# cree_lamp.net
KiCad netlist of a schematic drawn in Altium Designer
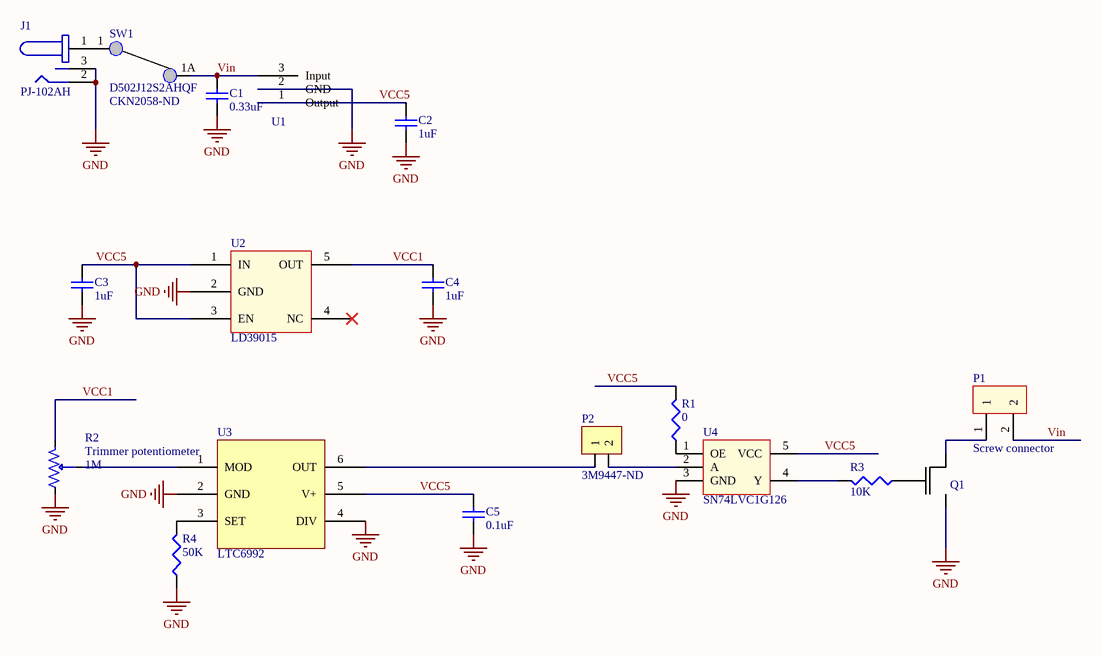
[diagram p0: cree_lamp.SchDoc]

(export (version "E")
  (design (tool "Eeschema 10.0.6"))
  (components
    (comp (ref "C1")
      (value "0.33uF")
      (footprint "1608[0603]")
      (description "Capacitor (Semiconductor SIM Model)")
      (fields (field (name "Comment") "Cap Semi") (field (name "PUBLISHER") "Altium Limited"))
      (libsource (lib "Miscellaneous Devices") (part "Cap Semi"))
    )
    (comp (ref "C2")
      (value "1uF")
      (footprint "1608[0603]")
      (description "Capacitor (Semiconductor SIM Model)")
      (fields (field (name "Comment") "Cap Semi") (field (name "PUBLISHER") "Altium Limited"))
      (libsource (lib "Miscellaneous Devices") (part "Cap Semi"))
    )
    (comp (ref "C3")
      (value "1uF")
      (footprint "1608[0603]")
      (description "Capacitor (Semiconductor SIM Model)")
      (fields (field (name "Comment") "Cap Semi") (field (name "PUBLISHER") "Altium Limited"))
      (libsource (lib "Miscellaneous Devices") (part "Cap Semi"))
    )
    (comp (ref "C4")
      (value "1uF")
      (footprint "1608[0603]")
      (description "Capacitor (Semiconductor SIM Model)")
      (fields (field (name "Comment") "Cap Semi") (field (name "PUBLISHER") "Altium Limited"))
      (libsource (lib "Miscellaneous Devices") (part "Cap Semi"))
    )
    (comp (ref "C5")
      (value "0.1uF")
      (footprint "1608[0603]")
      (description "Capacitor (Semiconductor SIM Model)")
      (fields (field (name "Comment") "Cap Semi") (field (name "PUBLISHER") "Altium Limited"))
      (libsource (lib "Miscellaneous Devices") (part "Cap Semi"))
    )
    (comp (ref "J1")
      (value "PJ-102AH")
      (footprint "PJ-102AH")
      (description "CONN PWR JACK 2.1X5.5MM HIGH CUR")
      (libsource (lib "vlc_ctrl") (part "PJ-102AH"))
    )
    (comp (ref "P1")
      (value "Screw connector")
      (footprint "MPT_2position")
      (description "Screw connector 2 positions")
      (libsource (lib "vlc_ctrl") (part "MPT_2POS"))
    )
    (comp (ref "P2")
      (value "1 x 2 header")
      (footprint "1x2 header")
      (description "100 mils standard header")
      (fields (field (name "SUPPLIER PART NUMBER 1") "3M9447-ND"))
      (libsource (lib "vlc_ctrl") (part "1 x 2 header"))
    )
    (comp (ref "Q1")
      (value "Si2312CDS")
      (footprint "SOT95P250-3N")
      (description "N-Channel 20 V (D-S) MOSFET")
      (libsource (lib "vlc_ctrl") (part "Si2312CDS"))
    )
    (comp (ref "R1")
      (value "0")
      (footprint "J1-0603")
      (description "Resistor")
      (fields (field (name "Comment") "Res3") (field (name "PUBLISHER") "Altium Limited"))
      (libsource (lib "Miscellaneous Devices") (part "Res3"))
    )
    (comp (ref "R2")
      (value "Trimmer potentiometer")
      (footprint "3386P")
      (fields (field (name "ALTIUM_VALUE") "1M"))
      (libsource (lib "Schlib1") (part "potentiometer"))
    )
    (comp (ref "R3")
      (value "10K")
      (footprint "J1-0603")
      (description "Resistor")
      (fields (field (name "Comment") "Res3") (field (name "PUBLISHER") "Altium Limited"))
      (libsource (lib "Miscellaneous Devices") (part "Res3"))
    )
    (comp (ref "R4")
      (value "50K")
      (footprint "J1-0603")
      (description "Resistor")
      (fields (field (name "Comment") "Res3") (field (name "PUBLISHER") "Altium Limited"))
      (libsource (lib "Miscellaneous Devices") (part "Res3"))
    )
    (comp (ref "SW1")
      (value "D502J12S2AHQF")
      (footprint "Rocker switch")
      (description "Miniature Snap-in Power Rocker Switches")
      (fields (field (name "SUPPLIER PART NUMBER 1") "CKN2058-ND"))
      (libsource (lib "acdc") (part "rocker switch"))
    )
    (comp (ref "U1")
      (value "LM78L05")
      (footprint "TO92")
      (description "LM78LXX Series 3-Terminal Positive Regulators")
      (libsource (lib "vlc_ctrl") (part "LM78L05"))
    )
    (comp (ref "U2")
      (value "LD39015")
      (footprint "SOT23-5")
      (description "150 mA low quiescent current and low noise voltage regulator")
      (libsource (lib "vlc_ctrl") (part "LD39015"))
    )
    (comp (ref "U3")
      (value "LTC6992")
      (footprint "TSOT23-6")
      (description "TimerBlox: Voltage-Controlled Pulse   Width Modulator (PWM)")
      (libsource (lib "VLC") (part "LTC6992"))
    )
    (comp (ref "U4")
      (value "SN74LVC1G126")
      (footprint "SOT23-5")
      (description "Single Bus Buffer Gate With 3-State Output")
      (libsource (lib "vlc_ctrl") (part "SN74LVC1G126"))
    )
  )
  (nets
    (net (code "1") (name "/VCC1") (class "Default")
      (node (ref "C4") (pin "2") (pinfunction "2_2") (pintype "passive"))
      (node (ref "R2") (pin "3") (pinfunction "3_3") (pintype "passive"))
      (node (ref "U2") (pin "5") (pinfunction "OUT_5") (pintype "passive"))
    )
    (net (code "2") (name "/VCC5") (class "Default")
      (node (ref "C2") (pin "2") (pinfunction "2_2") (pintype "passive"))
      (node (ref "C3") (pin "2") (pinfunction "2_2") (pintype "passive"))
      (node (ref "C5") (pin "2") (pinfunction "2_2") (pintype "passive"))
      (node (ref "R1") (pin "2") (pinfunction "2_2") (pintype "passive"))
      (node (ref "U1") (pin "1") (pinfunction "Output_1") (pintype "passive"))
      (node (ref "U2") (pin "1") (pinfunction "IN_1") (pintype "passive"))
      (node (ref "U2") (pin "3") (pinfunction "EN_3") (pintype "passive"))
      (node (ref "U3") (pin "5") (pinfunction "V+_5") (pintype "passive"))
      (node (ref "U4") (pin "5") (pinfunction "VCC_5") (pintype "passive"))
    )
    (net (code "3") (name "/Vin") (class "Default")
      (node (ref "C1") (pin "2") (pinfunction "2_2") (pintype "passive"))
      (node (ref "P1") (pin "2") (pinfunction "2_2") (pintype "passive"))
      (node (ref "SW1") (pin "1A") (pinfunction "2_1A") (pintype "passive"))
      (node (ref "U1") (pin "3") (pinfunction "Input_3") (pintype "passive"))
    )
    (net (code "4") (name "GND") (class "Default")
      (node (ref "C1") (pin "1") (pinfunction "1_1") (pintype "passive"))
      (node (ref "C2") (pin "1") (pinfunction "1_1") (pintype "passive"))
      (node (ref "C3") (pin "1") (pinfunction "1_1") (pintype "passive"))
      (node (ref "C4") (pin "1") (pinfunction "1_1") (pintype "passive"))
      (node (ref "C5") (pin "1") (pinfunction "1_1") (pintype "passive"))
      (node (ref "J1") (pin "2") (pintype "passive"))
      (node (ref "J1") (pin "3") (pintype "passive"))
      (node (ref "Q1") (pin "2") (pinfunction "S_2") (pintype "passive"))
      (node (ref "R2") (pin "1") (pinfunction "1_1") (pintype "passive"))
      (node (ref "R4") (pin "1") (pinfunction "1_1") (pintype "passive"))
      (node (ref "U1") (pin "2") (pinfunction "GND_2") (pintype "passive"))
      (node (ref "U2") (pin "2") (pinfunction "GND_2") (pintype "passive"))
      (node (ref "U3") (pin "2") (pinfunction "GND_2") (pintype "passive"))
      (node (ref "U3") (pin "4") (pinfunction "DIV_4") (pintype "passive"))
      (node (ref "U4") (pin "3") (pinfunction "GND_3") (pintype "passive"))
    )
    (net (code "5") (name "Net-(J1-Pad1)") (class "Default")
      (node (ref "J1") (pin "1") (pintype "passive"))
      (node (ref "SW1") (pin "1") (pinfunction "1_1") (pintype "passive"))
    )
    (net (code "6") (name "Net-(Q1-D)") (class "Default")
      (node (ref "P1") (pin "1") (pinfunction "1_1") (pintype "passive"))
      (node (ref "Q1") (pin "3") (pinfunction "D_3") (pintype "passive"))
    )
    (net (code "7") (name "Net-(Q1-G)") (class "Default")
      (node (ref "Q1") (pin "1") (pinfunction "G_1") (pintype "passive"))
      (node (ref "R3") (pin "1") (pinfunction "1_1") (pintype "passive"))
    )
    (net (code "8") (name "Net-(U3-MOD)") (class "Default")
      (node (ref "R2") (pin "2") (pinfunction "2_2") (pintype "passive"))
      (node (ref "U3") (pin "1") (pinfunction "MOD_1") (pintype "passive"))
    )
    (net (code "9") (name "Net-(U3-OUT)") (class "Default")
      (node (ref "P2") (pin "1") (pinfunction "1_1") (pintype "passive"))
      (node (ref "U3") (pin "6") (pinfunction "OUT_6") (pintype "passive"))
    )
    (net (code "10") (name "Net-(U3-SET)") (class "Default")
      (node (ref "R4") (pin "2") (pinfunction "2_2") (pintype "passive"))
      (node (ref "U3") (pin "3") (pinfunction "SET_3") (pintype "passive"))
    )
    (net (code "11") (name "Net-(U4-A)") (class "Default")
      (node (ref "P2") (pin "2") (pinfunction "2_2") (pintype "passive"))
      (node (ref "U4") (pin "2") (pinfunction "A_2") (pintype "passive"))
    )
    (net (code "12") (name "Net-(U4-OE)") (class "Default")
      (node (ref "R1") (pin "1") (pinfunction "1_1") (pintype "passive"))
      (node (ref "U4") (pin "1") (pinfunction "OE_1") (pintype "passive"))
    )
    (net (code "13") (name "Net-(U4-Y)") (class "Default")
      (node (ref "R3") (pin "2") (pinfunction "2_2") (pintype "passive"))
      (node (ref "U4") (pin "4") (pinfunction "Y_4") (pintype "passive"))
    )
    (net (code "14") (name "unconnected-(U2-NC-Pad4)") (class "Default")
      (node (ref "U2") (pin "4") (pinfunction "NC_4") (pintype "passive+no_connect"))
    )
  )
)
